# Adafruit_ItsyBitsy_ESP32.net
KiCad netlist of a schematic drawn in EAGLE
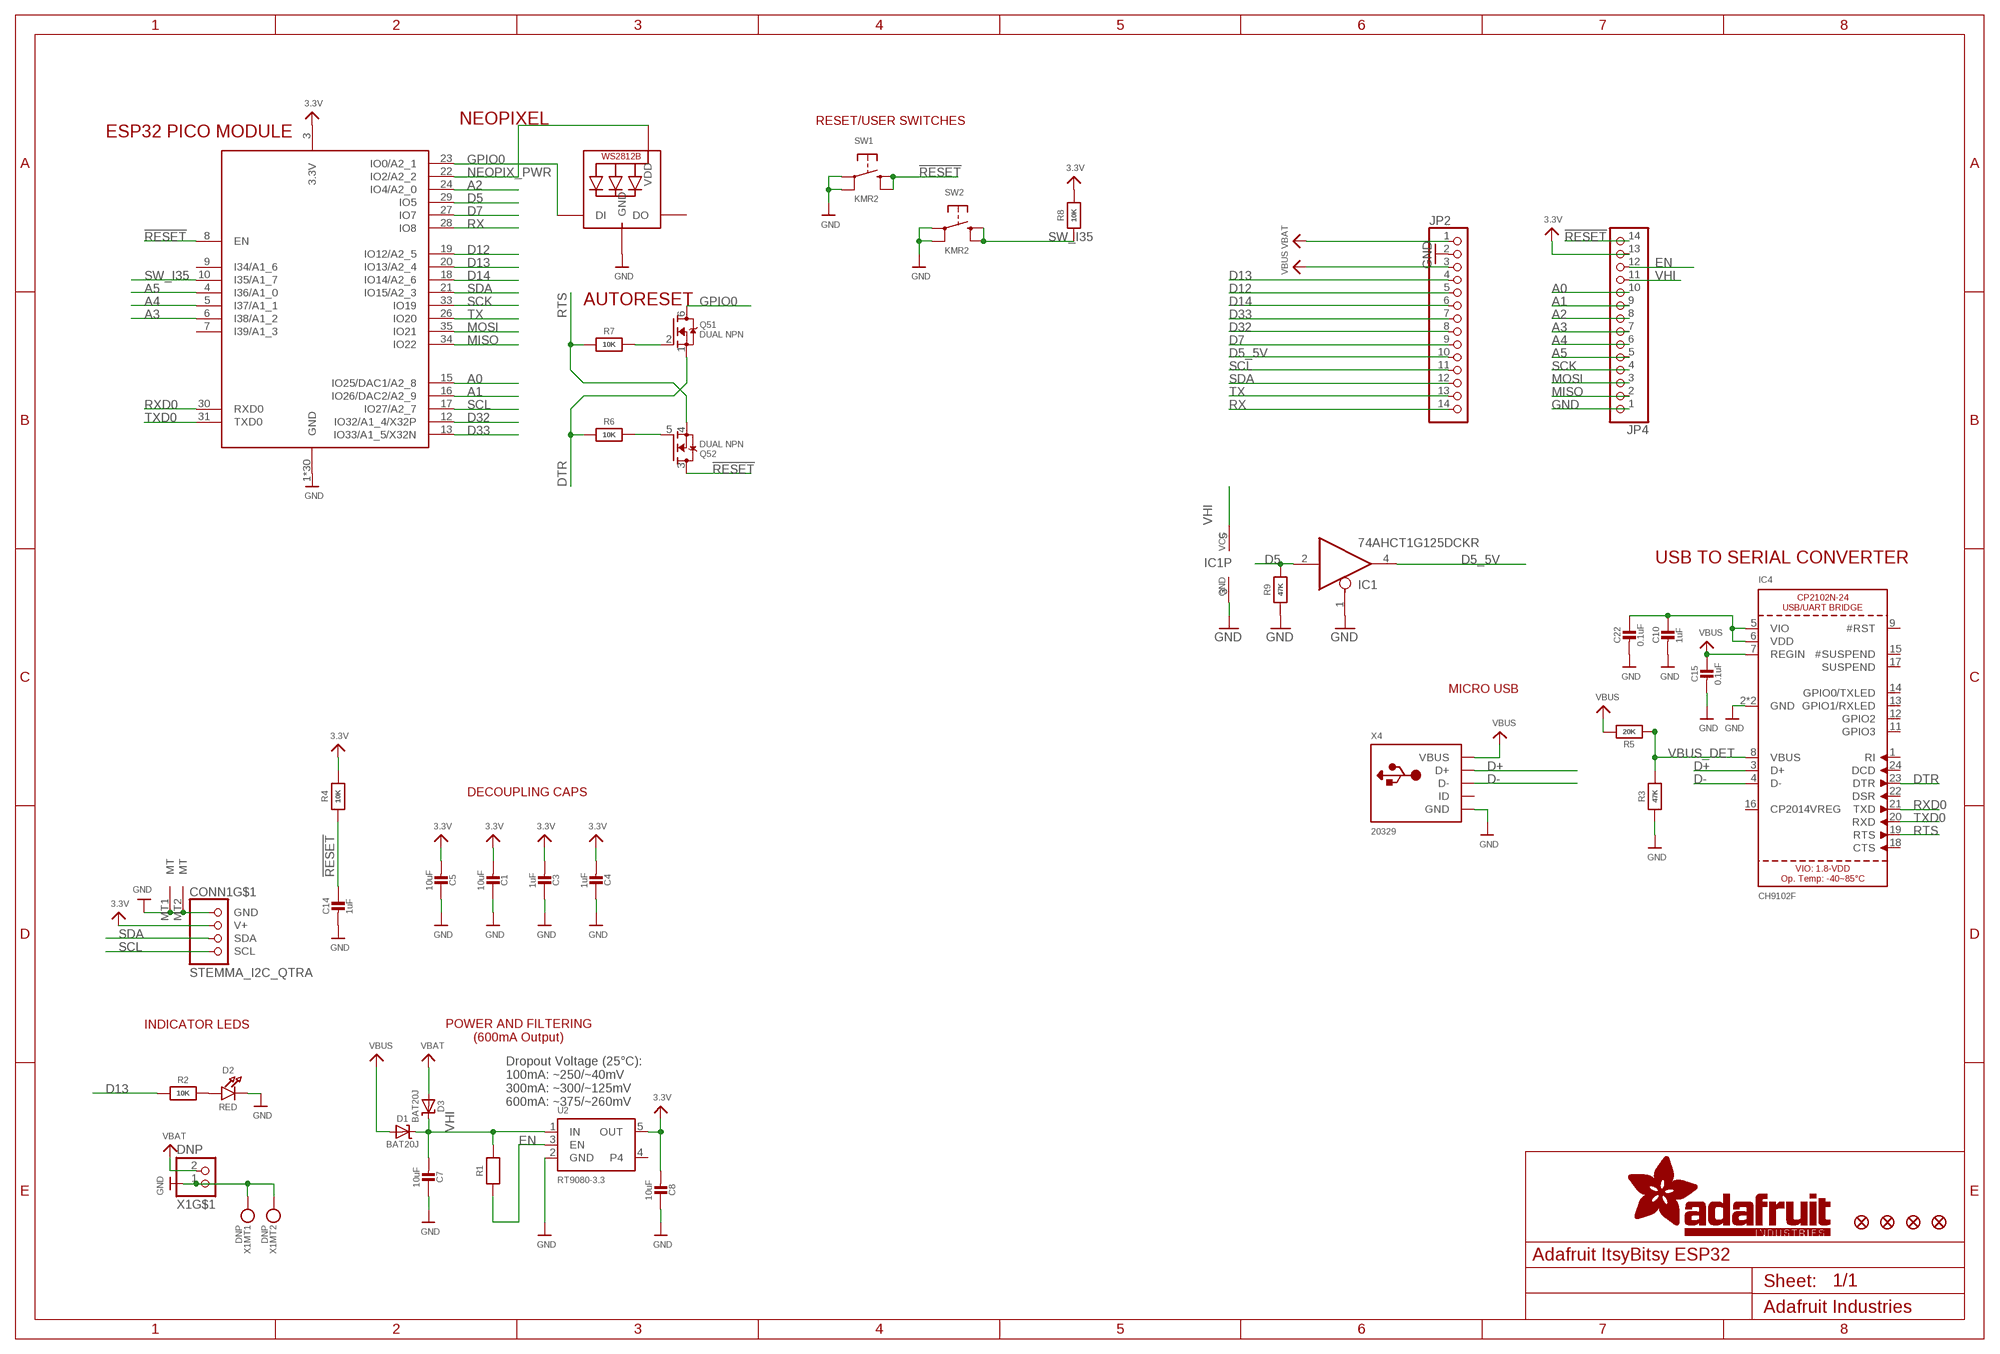
[diagram p0: schematic, sheet 1]

(export (version "E")
  (design (tool "Eeschema 10.0.6"))
  (components
    (comp (ref "C1")
      (value "10uF")
      (footprint "eagle-import:0805-NO")
      (libsource (lib "eagle-import") (part "CAP_CERAMIC0805-NOOUTLINE"))
    )
    (comp (ref "C3")
      (value "1uF")
      (footprint "eagle-import:0603-NO")
      (libsource (lib "eagle-import") (part "CAP_CERAMIC0603_NO"))
    )
    (comp (ref "C4")
      (value "1uF")
      (footprint "eagle-import:0603-NO")
      (libsource (lib "eagle-import") (part "CAP_CERAMIC0603_NO"))
    )
    (comp (ref "C5")
      (value "10uF")
      (footprint "eagle-import:0805-NO")
      (libsource (lib "eagle-import") (part "CAP_CERAMIC0805-NOOUTLINE"))
    )
    (comp (ref "C7")
      (value "10uF")
      (footprint "eagle-import:0805-NO")
      (libsource (lib "eagle-import") (part "CAP_CERAMIC0805-NOOUTLINE"))
    )
    (comp (ref "C8")
      (value "10uF")
      (footprint "eagle-import:0805-NO")
      (libsource (lib "eagle-import") (part "CAP_CERAMIC0805-NOOUTLINE"))
    )
    (comp (ref "C10")
      (value "1uF")
      (footprint "eagle-import:0603-NO")
      (libsource (lib "eagle-import") (part "CAP_CERAMIC0603_NO"))
    )
    (comp (ref "C14")
      (value "1uF")
      (footprint "eagle-import:0603-NO")
      (libsource (lib "eagle-import") (part "CAP_CERAMIC0603_NO"))
    )
    (comp (ref "C15")
      (value "0.1uF")
      (footprint "eagle-import:0603-NO")
      (libsource (lib "eagle-import") (part "CAP_CERAMIC0603_NO"))
    )
    (comp (ref "C22")
      (value "0.1uF")
      (footprint "eagle-import:0603-NO")
      (libsource (lib "eagle-import") (part "CAP_CERAMIC0603_NO"))
    )
    (comp (ref "CONN1")
      (value "STEMMA_I2C_QTRA")
      (footprint "eagle-import:JST_SH4_RA")
      (libsource (lib "eagle-import") (part "STEMMA_I2C_QTRA"))
    )
    (comp (ref "D1")
      (value "BAT20J")
      (footprint "eagle-import:SOD-323")
      (libsource (lib "eagle-import") (part "DIODE-SCHOTTKYSOD-323"))
    )
    (comp (ref "D2")
      (value "RED")
      (footprint "eagle-import:CHIPLED_0603_NOOUTLINE")
      (libsource (lib "eagle-import") (part "LED0603_NOOUTLINE"))
    )
    (comp (ref "D3")
      (value "BAT20J")
      (footprint "eagle-import:SOD-323")
      (libsource (lib "eagle-import") (part "DIODE-SCHOTTKYSOD-323"))
    )
    (comp (ref "FID1")
      (value "FIDUCIAL_1MM")
      (footprint "eagle-import:FIDUCIAL_1MM")
      (libsource (lib "eagle-import") (part "FIDUCIAL_1MM"))
    )
    (comp (ref "FID2")
      (value "FIDUCIAL_1MM")
      (footprint "eagle-import:FIDUCIAL_1MM")
      (libsource (lib "eagle-import") (part "FIDUCIAL_1MM"))
    )
    (comp (ref "FID3")
      (value "FIDUCIAL_1MM")
      (footprint "eagle-import:FIDUCIAL_1MM")
      (libsource (lib "eagle-import") (part "FIDUCIAL_1MM"))
    )
    (comp (ref "FID4")
      (value "FIDUCIAL_1MM")
      (footprint "eagle-import:FIDUCIAL_1MM")
      (libsource (lib "eagle-import") (part "FIDUCIAL_1MM"))
    )
    (comp (ref "IC1")
      (value "74AHCT1G125DCKR")
      (footprint "eagle-import:SC70-5")
      (libsource (lib "eagle-import") (part "741G125DCKAHC"))
    )
    (comp (ref "IC4")
      (value "CH9102F")
      (footprint "eagle-import:QFN24_4MM_SMSC")
      (libsource (lib "eagle-import") (part "CP2102N-24"))
    )
    (comp (ref "JP2")
      (value "HEADER-1X14")
      (footprint "eagle-import:1X14_ROUND70")
      (libsource (lib "eagle-import") (part "HEADER-1X14"))
    )
    (comp (ref "JP4")
      (value "HEADER-1X14")
      (footprint "eagle-import:1X14_ROUND70")
      (libsource (lib "eagle-import") (part "HEADER-1X14"))
    )
    (comp (ref "LED2")
      (value "WS2812B_SK6805_1515")
      (footprint "eagle-import:SK6805_1515")
      (libsource (lib "eagle-import") (part "WS2812B_SK6805_1515"))
    )
    (comp (ref "Q5")
      (value "DUAL NPN")
      (footprint "eagle-import:SOT363")
      (fields (field (name "JLC_ROTATION") "0"))
      (libsource (lib "eagle-import") (part "MOSFET-N_DUAL"))
    )
    (comp (ref "R1")
      (value "10K")
      (footprint "eagle-import:0603-NO")
      (libsource (lib "eagle-import") (part "RESISTOR_0603_NOOUT"))
    )
    (comp (ref "R2")
      (value "10K")
      (footprint "eagle-import:0603-NO")
      (libsource (lib "eagle-import") (part "RESISTOR_0603_NOOUT"))
    )
    (comp (ref "R3")
      (value "47K")
      (footprint "eagle-import:0603-NO")
      (libsource (lib "eagle-import") (part "RESISTOR_0603_NOOUT"))
    )
    (comp (ref "R4")
      (value "10K")
      (footprint "eagle-import:0603-NO")
      (libsource (lib "eagle-import") (part "RESISTOR_0603_NOOUT"))
    )
    (comp (ref "R5")
      (value "20K")
      (footprint "eagle-import:0603-NO")
      (libsource (lib "eagle-import") (part "RESISTOR_0603_NOOUT"))
    )
    (comp (ref "R6")
      (value "10K")
      (footprint "eagle-import:0603-NO")
      (libsource (lib "eagle-import") (part "RESISTOR_0603_NOOUT"))
    )
    (comp (ref "R7")
      (value "10K")
      (footprint "eagle-import:0603-NO")
      (libsource (lib "eagle-import") (part "RESISTOR_0603_NOOUT"))
    )
    (comp (ref "R8")
      (value "10K")
      (footprint "eagle-import:0603-NO")
      (libsource (lib "eagle-import") (part "RESISTOR_0603_NOOUT"))
    )
    (comp (ref "R9")
      (value "47K")
      (footprint "eagle-import:0603-NO")
      (libsource (lib "eagle-import") (part "RESISTOR_0603_NOOUT"))
    )
    (comp (ref "SW1")
      (value "KMR2")
      (footprint "eagle-import:BTN_RKB2_4.6X2.8")
      (libsource (lib "eagle-import") (part "SWITCH_TACT_SMT_RKB2"))
    )
    (comp (ref "SW2")
      (value "KMR2")
      (footprint "eagle-import:BTN_RKB2_4.6X2.8")
      (libsource (lib "eagle-import") (part "SWITCH_TACT_SMT_RKB2"))
    )
    (comp (ref "U2")
      (value "RT9080-3.3")
      (footprint "eagle-import:SOT23-5")
      (fields (field (name "JLC_ROTATION") "0"))
      (libsource (lib "eagle-import") (part "VREG_SOT23-5"))
    )
    (comp (ref "X1")
      (value "DNP")
      (footprint "eagle-import:JSTPH2_BATT")
      (libsource (lib "eagle-import") (part "CON_JST_PH_2PIN_MT_BATT"))
    )
    (comp (ref "X3")
      (value "ESP32-PICO-MINI-02MINI")
      (footprint "eagle-import:ESP32-PICO-MINI")
      (libsource (lib "eagle-import") (part "ESP32-PICO-MINI-02MINI"))
    )
    (comp (ref "X4")
      (value "20329")
      (footprint "eagle-import:4UCONN_20329_SLIM")
      (libsource (lib "eagle-import") (part "USB_SLIM"))
    )
  )
  (nets
    (net (code "1") (name "/A0") (class "Default")
      (node (ref "JP4") (pin "10") (pinfunction "10_10") (pintype "passive"))
      (node (ref "X3") (pin "15") (pinfunction "IO25/DAC1/A2_8_15") (pintype "bidirectional"))
    )
    (net (code "2") (name "/A1") (class "Default")
      (node (ref "JP4") (pin "9") (pinfunction "9_9") (pintype "passive"))
      (node (ref "X3") (pin "16") (pinfunction "IO26/DAC2/A2_9_16") (pintype "bidirectional"))
    )
    (net (code "3") (name "/A2") (class "Default")
      (node (ref "JP4") (pin "8") (pinfunction "8_8") (pintype "passive"))
      (node (ref "X3") (pin "24") (pinfunction "IO4/A2_0_24") (pintype "bidirectional"))
    )
    (net (code "4") (name "/A3") (class "Default")
      (node (ref "JP4") (pin "7") (pinfunction "7_7") (pintype "passive"))
      (node (ref "X3") (pin "6") (pinfunction "I38/A1_2_6") (pintype "input"))
    )
    (net (code "5") (name "/A4") (class "Default")
      (node (ref "JP4") (pin "6") (pinfunction "6_6") (pintype "passive"))
      (node (ref "X3") (pin "5") (pinfunction "I37/A1_1_5") (pintype "input"))
    )
    (net (code "6") (name "/A5") (class "Default")
      (node (ref "JP4") (pin "5") (pinfunction "5_5") (pintype "passive"))
      (node (ref "X3") (pin "4") (pinfunction "I36/A1_0_4") (pintype "input"))
    )
    (net (code "7") (name "/D+") (class "Default")
      (node (ref "IC4") (pin "3") (pinfunction "D+_3") (pintype "bidirectional"))
      (node (ref "X4") (pin "D+") (pinfunction "D+_D+") (pintype "bidirectional"))
    )
    (net (code "8") (name "/D-") (class "Default")
      (node (ref "IC4") (pin "4") (pinfunction "D-_4") (pintype "bidirectional"))
      (node (ref "X4") (pin "D-") (pinfunction "D-_D-") (pintype "bidirectional"))
    )
    (net (code "9") (name "/D5") (class "Default")
      (node (ref "IC1") (pin "2") (pinfunction "I_2") (pintype "input"))
      (node (ref "R9") (pin "2") (pinfunction "2_2") (pintype "passive"))
      (node (ref "X3") (pin "29") (pinfunction "IO5_29") (pintype "bidirectional"))
    )
    (net (code "10") (name "/D5_5V") (class "Default")
      (node (ref "IC1") (pin "4") (pinfunction "O_4") (pintype "tri_state"))
      (node (ref "JP2") (pin "10") (pinfunction "10_10") (pintype "passive"))
    )
    (net (code "11") (name "/D7") (class "Default")
      (node (ref "JP2") (pin "9") (pinfunction "9_9") (pintype "passive"))
      (node (ref "X3") (pin "27") (pinfunction "IO7_27") (pintype "bidirectional"))
    )
    (net (code "12") (name "/D12") (class "Default")
      (node (ref "JP2") (pin "5") (pinfunction "5_5") (pintype "passive"))
      (node (ref "X3") (pin "19") (pinfunction "IO12/A2_5_19") (pintype "bidirectional"))
    )
    (net (code "13") (name "/D13") (class "Default")
      (node (ref "JP2") (pin "4") (pinfunction "4_4") (pintype "passive"))
      (node (ref "R2") (pin "1") (pinfunction "1_1") (pintype "passive"))
      (node (ref "X3") (pin "20") (pinfunction "IO13/A2_4_20") (pintype "bidirectional"))
    )
    (net (code "14") (name "/D14") (class "Default")
      (node (ref "JP2") (pin "6") (pinfunction "6_6") (pintype "passive"))
      (node (ref "X3") (pin "18") (pinfunction "IO14/A2_6_18") (pintype "bidirectional"))
    )
    (net (code "15") (name "/D32") (class "Default")
      (node (ref "JP2") (pin "8") (pinfunction "8_8") (pintype "passive"))
      (node (ref "X3") (pin "12") (pinfunction "IO32/A1_4/X32P_12") (pintype "bidirectional"))
    )
    (net (code "16") (name "/D33") (class "Default")
      (node (ref "JP2") (pin "7") (pinfunction "7_7") (pintype "passive"))
      (node (ref "X3") (pin "13") (pinfunction "IO33/A1_5/X32N_13") (pintype "bidirectional"))
    )
    (net (code "17") (name "/DTR") (class "Default")
      (node (ref "IC4") (pin "23") (pinfunction "DTR_23") (pintype "output"))
      (node (ref "Q5") (pin "1") (pinfunction "S_1") (pintype "bidirectional"))
      (node (ref "R6") (pin "1") (pinfunction "1_1") (pintype "passive"))
    )
    (net (code "18") (name "/EN") (class "Default")
      (node (ref "JP4") (pin "12") (pinfunction "12_12") (pintype "passive"))
      (node (ref "R1") (pin "1") (pinfunction "1_1") (pintype "passive"))
      (node (ref "U2") (pin "3") (pinfunction "EN_3") (pintype "input"))
    )
    (net (code "19") (name "/GPIO0") (class "Default")
      (node (ref "LED2") (pin "1") (pinfunction "DI_1") (pintype "input"))
      (node (ref "Q5") (pin "6") (pinfunction "D_6") (pintype "bidirectional"))
      (node (ref "X3") (pin "23") (pinfunction "IO0/A2_1_23") (pintype "bidirectional"))
    )
    (net (code "20") (name "/MISO") (class "Default")
      (node (ref "JP4") (pin "2") (pinfunction "2_2") (pintype "passive"))
      (node (ref "X3") (pin "34") (pinfunction "IO22_34") (pintype "bidirectional"))
    )
    (net (code "21") (name "/MOSI") (class "Default")
      (node (ref "JP4") (pin "3") (pinfunction "3_3") (pintype "passive"))
      (node (ref "X3") (pin "35") (pinfunction "IO21_35") (pintype "bidirectional"))
    )
    (net (code "22") (name "/NEOPIX_PWR") (class "Default")
      (node (ref "LED2") (pin "2") (pinfunction "VDD_2") (pintype "power_in"))
      (node (ref "X3") (pin "22") (pinfunction "IO2/A2_2_22") (pintype "bidirectional"))
    )
    (net (code "23") (name "/RTS") (class "Default")
      (node (ref "IC4") (pin "19") (pinfunction "RTS_19") (pintype "output"))
      (node (ref "Q5") (pin "4") (pinfunction "S_4") (pintype "bidirectional"))
      (node (ref "R7") (pin "1") (pinfunction "1_1") (pintype "passive"))
    )
    (net (code "24") (name "/RX") (class "Default")
      (node (ref "JP2") (pin "14") (pinfunction "14_14") (pintype "passive"))
      (node (ref "X3") (pin "28") (pinfunction "IO8_28") (pintype "bidirectional"))
    )
    (net (code "25") (name "/RXD0") (class "Default")
      (node (ref "IC4") (pin "21") (pinfunction "TXD_21") (pintype "output"))
      (node (ref "X3") (pin "30") (pinfunction "RXD0_30") (pintype "input"))
    )
    (net (code "26") (name "/SCK") (class "Default")
      (node (ref "JP4") (pin "4") (pinfunction "4_4") (pintype "passive"))
      (node (ref "X3") (pin "33") (pinfunction "IO19_33") (pintype "bidirectional"))
    )
    (net (code "27") (name "/SCL") (class "Default")
      (node (ref "CONN1") (pin "4") (pinfunction "SCL_4") (pintype "passive"))
      (node (ref "JP2") (pin "11") (pinfunction "11_11") (pintype "passive"))
      (node (ref "X3") (pin "17") (pinfunction "IO27/A2_7_17") (pintype "bidirectional"))
    )
    (net (code "28") (name "/SDA") (class "Default")
      (node (ref "CONN1") (pin "3") (pinfunction "SDA_3") (pintype "passive"))
      (node (ref "JP2") (pin "12") (pinfunction "12_12") (pintype "passive"))
      (node (ref "X3") (pin "21") (pinfunction "IO15/A2_3_21") (pintype "bidirectional"))
    )
    (net (code "29") (name "/SW_I35") (class "Default")
      (node (ref "R8") (pin "1") (pinfunction "1_1") (pintype "passive"))
      (node (ref "SW2") (pin "B") (pinfunction "S_B") (pintype "passive"))
      (node (ref "SW2") (pin "B'") (pinfunction "S1_B'") (pintype "passive"))
      (node (ref "X3") (pin "10") (pinfunction "I35/A1_7_10") (pintype "input"))
    )
    (net (code "30") (name "/TX") (class "Default")
      (node (ref "JP2") (pin "13") (pinfunction "13_13") (pintype "passive"))
      (node (ref "X3") (pin "26") (pinfunction "IO20_26") (pintype "bidirectional"))
    )
    (net (code "31") (name "/TXD0") (class "Default")
      (node (ref "IC4") (pin "20") (pinfunction "RXD_20") (pintype "input"))
      (node (ref "X3") (pin "31") (pinfunction "TXD0_31") (pintype "output"))
    )
    (net (code "32") (name "/VBUS_DET") (class "Default")
      (node (ref "IC4") (pin "8") (pinfunction "VBUS_8") (pintype "power_in"))
      (node (ref "R3") (pin "2") (pinfunction "2_2") (pintype "passive"))
      (node (ref "R5") (pin "1") (pinfunction "1_1") (pintype "passive"))
    )
    (net (code "33") (name "/VHI") (class "Default")
      (node (ref "C7") (pin "2") (pinfunction "2_2") (pintype "passive"))
      (node (ref "D1") (pin "C") (pinfunction "C_C") (pintype "passive"))
      (node (ref "D3") (pin "C") (pinfunction "C_C") (pintype "passive"))
      (node (ref "IC1") (pin "5") (pinfunction "VCC_5") (pintype "power_in"))
      (node (ref "JP4") (pin "11") (pinfunction "11_11") (pintype "passive"))
      (node (ref "R1") (pin "2") (pinfunction "2_2") (pintype "passive"))
      (node (ref "U2") (pin "1") (pinfunction "IN_1") (pintype "power_in"))
    )
    (net (code "34") (name "/~{RESET}") (class "Default")
      (node (ref "C14") (pin "1") (pinfunction "1_1") (pintype "passive"))
      (node (ref "JP4") (pin "14") (pinfunction "14_14") (pintype "passive"))
      (node (ref "Q5") (pin "3") (pinfunction "D_3") (pintype "bidirectional"))
      (node (ref "R4") (pin "1") (pinfunction "1_1") (pintype "passive"))
      (node (ref "SW1") (pin "B") (pinfunction "S_B") (pintype "passive"))
      (node (ref "SW1") (pin "B'") (pinfunction "S1_B'") (pintype "passive"))
      (node (ref "X3") (pin "8") (pinfunction "EN_8") (pintype "input"))
    )
    (net (code "35") (name "3.3V") (class "Default")
      (node (ref "C1") (pin "2") (pinfunction "2_2") (pintype "passive"))
      (node (ref "C3") (pin "2") (pinfunction "2_2") (pintype "passive"))
      (node (ref "C4") (pin "2") (pinfunction "2_2") (pintype "passive"))
      (node (ref "C5") (pin "2") (pinfunction "2_2") (pintype "passive"))
      (node (ref "C8") (pin "2") (pinfunction "2_2") (pintype "passive"))
      (node (ref "CONN1") (pin "2") (pinfunction "V+_2") (pintype "passive"))
      (node (ref "JP4") (pin "13") (pinfunction "13_13") (pintype "passive"))
      (node (ref "R4") (pin "2") (pinfunction "2_2") (pintype "passive"))
      (node (ref "R8") (pin "2") (pinfunction "2_2") (pintype "passive"))
      (node (ref "U2") (pin "5") (pinfunction "OUT_5") (pintype "power_in"))
      (node (ref "X3") (pin "3") (pinfunction "3.3V_3") (pintype "passive"))
    )
    (net (code "36") (name "GND") (class "Default")
      (node (ref "C1") (pin "1") (pinfunction "1_1") (pintype "passive"))
      (node (ref "C10") (pin "2") (pinfunction "2_2") (pintype "passive"))
      (node (ref "C14") (pin "2") (pinfunction "2_2") (pintype "passive"))
      (node (ref "C15") (pin "2") (pinfunction "2_2") (pintype "passive"))
      (node (ref "C22") (pin "2") (pinfunction "2_2") (pintype "passive"))
      (node (ref "C3") (pin "1") (pinfunction "1_1") (pintype "passive"))
      (node (ref "C4") (pin "1") (pinfunction "1_1") (pintype "passive"))
      (node (ref "C5") (pin "1") (pinfunction "1_1") (pintype "passive"))
      (node (ref "C7") (pin "1") (pinfunction "1_1") (pintype "passive"))
      (node (ref "C8") (pin "1") (pinfunction "1_1") (pintype "passive"))
      (node (ref "CONN1") (pin "1") (pinfunction "GND_1") (pintype "passive"))
      (node (ref "CONN1") (pin "MT1") (pinfunction "MT_MT1") (pintype "bidirectional"))
      (node (ref "CONN1") (pin "MT2") (pinfunction "MT_MT2") (pintype "bidirectional"))
      (node (ref "D2") (pin "C") (pinfunction "C_C") (pintype "passive"))
      (node (ref "IC1") (pin "1") (pinfunction "OE_1") (pintype "input"))
      (node (ref "IC1") (pin "3") (pinfunction "GND_3") (pintype "power_in"))
      (node (ref "IC4") (pin "2") (pinfunction "GND_2") (pintype "power_in"))
      (node (ref "IC4") (pin "THERM") (pinfunction "GND_THERM") (pintype "power_in"))
      (node (ref "JP2") (pin "2") (pinfunction "2_2") (pintype "passive"))
      (node (ref "JP4") (pin "1") (pinfunction "1_1") (pintype "passive"))
      (node (ref "LED2") (pin "4") (pinfunction "GND_4") (pintype "power_in"))
      (node (ref "R3") (pin "1") (pinfunction "1_1") (pintype "passive"))
      (node (ref "R9") (pin "1") (pinfunction "1_1") (pintype "passive"))
      (node (ref "SW1") (pin "A") (pinfunction "P_A") (pintype "passive"))
      (node (ref "SW1") (pin "A'") (pinfunction "P1_A'") (pintype "passive"))
      (node (ref "SW2") (pin "A") (pinfunction "P_A") (pintype "passive"))
      (node (ref "SW2") (pin "A'") (pinfunction "P1_A'") (pintype "passive"))
      (node (ref "U2") (pin "2") (pinfunction "GND_2") (pintype "power_in"))
      (node (ref "X1") (pin "1") (pinfunction "1_1") (pintype "passive"))
      (node (ref "X1") (pin "NC1") (pinfunction "P$1_NC1") (pintype "bidirectional"))
      (node (ref "X1") (pin "NC2") (pinfunction "P$1_NC2") (pintype "bidirectional"))
      (node (ref "X3") (pin "1") (pinfunction "GND_1") (pintype "passive"))
      (node (ref "X3") (pin "11") (pinfunction "GND_11") (pintype "passive"))
      (node (ref "X3") (pin "14") (pinfunction "GND_14") (pintype "passive"))
      (node (ref "X3") (pin "2") (pinfunction "GND_2") (pintype "passive"))
      (node (ref "X3") (pin "36") (pinfunction "GND_36") (pintype "passive"))
      (node (ref "X3") (pin "37") (pinfunction "GND_37") (pintype "passive"))
      (node (ref "X3") (pin "38") (pinfunction "GND_38") (pintype "passive"))
      (node (ref "X3") (pin "39") (pinfunction "GND_39") (pintype "passive"))
      (node (ref "X3") (pin "40") (pinfunction "GND_40") (pintype "passive"))
      (node (ref "X3") (pin "41") (pinfunction "GND_41") (pintype "passive"))
      (node (ref "X3") (pin "42") (pinfunction "GND_42") (pintype "passive"))
      (node (ref "X3") (pin "43") (pinfunction "GND_43") (pintype "passive"))
      (node (ref "X3") (pin "44") (pinfunction "GND_44") (pintype "passive"))
      (node (ref "X3") (pin "45") (pinfunction "GND_45") (pintype "passive"))
      (node (ref "X3") (pin "46") (pinfunction "GND_46") (pintype "passive"))
      (node (ref "X3") (pin "47") (pinfunction "GND_47") (pintype "passive"))
      (node (ref "X3") (pin "48") (pinfunction "GND_48") (pintype "passive"))
      (node (ref "X3") (pin "49") (pinfunction "GND_49") (pintype "passive"))
      (node (ref "X3") (pin "50") (pinfunction "GND_50") (pintype "passive"))
      (node (ref "X3") (pin "51") (pinfunction "GND_51") (pintype "passive"))
      (node (ref "X3") (pin "52") (pinfunction "GND_52") (pintype "passive"))
      (node (ref "X3") (pin "53") (pinfunction "GND_53") (pintype "passive"))
      (node (ref "X3") (pin "54") (pinfunction "GND_54") (pintype "passive"))
      (node (ref "X3") (pin "55") (pinfunction "GND_55") (pintype "passive"))
      (node (ref "X3") (pin "56") (pinfunction "GND_56") (pintype "passive"))
      (node (ref "X3") (pin "57") (pinfunction "GND_57") (pintype "passive"))
      (node (ref "X3") (pin "58") (pinfunction "GND_58") (pintype "passive"))
      (node (ref "X3") (pin "59") (pinfunction "GND_59") (pintype "passive"))
      (node (ref "X3") (pin "60") (pinfunction "GND_60") (pintype "passive"))
      (node (ref "X3") (pin "61") (pinfunction "GND_61") (pintype "passive"))
      (node (ref "X4") (pin "BASE@1") (pinfunction "GND_BASE@1") (pintype "power_in"))
      (node (ref "X4") (pin "BASE@2") (pinfunction "GND_BASE@2") (pintype "power_in"))
      (node (ref "X4") (pin "GND") (pinfunction "GND_GND") (pintype "power_in"))
      (node (ref "X4") (pin "SPRT@1") (pinfunction "GND_SPRT@1") (pintype "power_in"))
      (node (ref "X4") (pin "SPRT@2") (pinfunction "GND_SPRT@2") (pintype "power_in"))
      (node (ref "X4") (pin "SPRT@3") (pinfunction "GND_SPRT@3") (pintype "power_in"))
      (node (ref "X4") (pin "SPRT@4") (pinfunction "GND_SPRT@4") (pintype "power_in"))
    )
    (net (code "37") (name "Net-(D2-PadA)") (class "Default")
      (node (ref "D2") (pin "A") (pinfunction "A_A") (pintype "passive"))
      (node (ref "R2") (pin "2") (pinfunction "2_2") (pintype "passive"))
    )
    (net (code "38") (name "Net-(IC4-VDD)") (class "Default")
      (node (ref "C10") (pin "1") (pinfunction "1_1") (pintype "passive"))
      (node (ref "C22") (pin "1") (pinfunction "1_1") (pintype "passive"))
      (node (ref "IC4") (pin "5") (pinfunction "VIO_5") (pintype "power_in"))
      (node (ref "IC4") (pin "6") (pinfunction "VDD_6") (pintype "power_in"))
    )
    (net (code "39") (name "Net-(Q5A-G)") (class "Default")
      (node (ref "Q5") (pin "2") (pinfunction "G_2") (pintype "bidirectional"))
      (node (ref "R7") (pin "2") (pinfunction "2_2") (pintype "passive"))
    )
    (net (code "40") (name "Net-(Q5B-G)") (class "Default")
      (node (ref "Q5") (pin "5") (pinfunction "G_5") (pintype "bidirectional"))
      (node (ref "R6") (pin "2") (pinfunction "2_2") (pintype "passive"))
    )
    (net (code "41") (name "VBAT") (class "Default")
      (node (ref "D3") (pin "A") (pinfunction "A_A") (pintype "passive"))
      (node (ref "JP2") (pin "1") (pinfunction "1_1") (pintype "passive"))
      (node (ref "X1") (pin "2") (pinfunction "2_2") (pintype "passive"))
    )
    (net (code "42") (name "VBUS") (class "Default")
      (node (ref "C15") (pin "1") (pinfunction "1_1") (pintype "passive"))
      (node (ref "D1") (pin "A") (pinfunction "A_A") (pintype "passive"))
      (node (ref "IC4") (pin "7") (pinfunction "REGIN_7") (pintype "power_in"))
      (node (ref "JP2") (pin "3") (pinfunction "3_3") (pintype "passive"))
      (node (ref "R5") (pin "2") (pinfunction "2_2") (pintype "passive"))
      (node (ref "X4") (pin "VBUS") (pinfunction "VBUS_VBUS") (pintype "power_in"))
    )
    (net (code "43") (name "unconnected-(IC4-#RST-Pad9)") (class "Default")
      (node (ref "IC4") (pin "9") (pinfunction "#RST_9") (pintype "bidirectional"))
    )
    (net (code "44") (name "unconnected-(IC4-#SUSPEND-Pad15)") (class "Default")
      (node (ref "IC4") (pin "15") (pinfunction "#SUSPEND_15") (pintype "output"))
    )
    (net (code "45") (name "unconnected-(IC4-CP2014VREG-Pad16)") (class "Default")
      (node (ref "IC4") (pin "16") (pinfunction "CP2014VREG_16") (pintype "passive"))
    )
    (net (code "46") (name "unconnected-(IC4-CTS-Pad18)") (class "Default")
      (node (ref "IC4") (pin "18") (pinfunction "CTS_18") (pintype "input"))
    )
    (net (code "47") (name "unconnected-(IC4-DCD-Pad24)") (class "Default")
      (node (ref "IC4") (pin "24") (pinfunction "DCD_24") (pintype "input"))
    )
    (net (code "48") (name "unconnected-(IC4-DSR-Pad22)") (class "Default")
      (node (ref "IC4") (pin "22") (pinfunction "DSR_22") (pintype "input"))
    )
    (net (code "49") (name "unconnected-(IC4-GPIO0{slash}TXLED-Pad14)") (class "Default")
      (node (ref "IC4") (pin "14") (pinfunction "GPIO0/TXLED_14") (pintype "bidirectional"))
    )
    (net (code "50") (name "unconnected-(IC4-GPIO1{slash}RXLED-Pad13)") (class "Default")
      (node (ref "IC4") (pin "13") (pinfunction "GPIO1/RXLED_13") (pintype "bidirectional"))
    )
    (net (code "51") (name "unconnected-(IC4-GPIO2-Pad12)") (class "Default")
      (node (ref "IC4") (pin "12") (pinfunction "GPIO2_12") (pintype "bidirectional"))
    )
    (net (code "52") (name "unconnected-(IC4-GPIO3-Pad11)") (class "Default")
      (node (ref "IC4") (pin "11") (pinfunction "GPIO3_11") (pintype "bidirectional"))
    )
    (net (code "53") (name "unconnected-(IC4-RI-Pad1)") (class "Default")
      (node (ref "IC4") (pin "1") (pinfunction "RI_1") (pintype "input"))
    )
    (net (code "54") (name "unconnected-(IC4-SUSPEND-Pad17)") (class "Default")
      (node (ref "IC4") (pin "17") (pinfunction "SUSPEND_17") (pintype "output"))
    )
    (net (code "55") (name "unconnected-(LED2-DO-Pad3)") (class "Default")
      (node (ref "LED2") (pin "3") (pinfunction "DO_3") (pintype "output"))
    )
    (net (code "56") (name "unconnected-(U2-P4-Pad4)") (class "Default")
      (node (ref "U2") (pin "4") (pinfunction "P4_4") (pintype "bidirectional"))
    )
    (net (code "57") (name "unconnected-(X3-I34{slash}A1_6-Pad9)") (class "Default")
      (node (ref "X3") (pin "9") (pinfunction "I34/A1_6_9") (pintype "input"))
    )
    (net (code "58") (name "unconnected-(X3-I39{slash}A1_3-Pad7)") (class "Default")
      (node (ref "X3") (pin "7") (pinfunction "I39/A1_3_7") (pintype "input"))
    )
    (net (code "59") (name "unconnected-(X4-PadID)") (class "Default")
      (node (ref "X4") (pin "ID") (pinfunction "ID_ID") (pintype "bidirectional"))
    )
  )
)
